# Xenon_Light.net
KiCad netlist of a schematic drawn in EAGLE
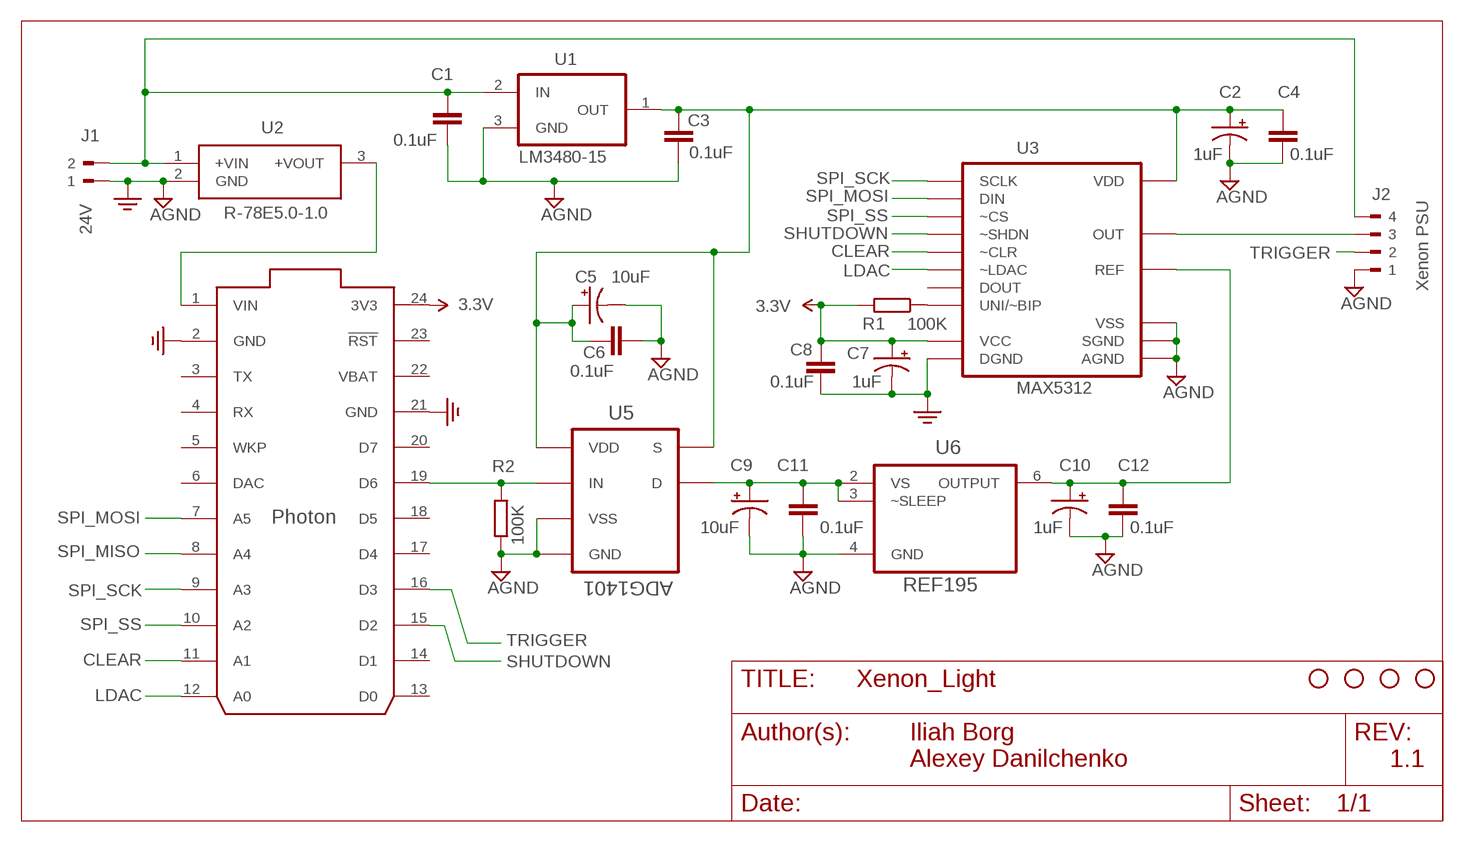
[diagram p0: schematic, sheet 1]

(export (version "E")
  (design (tool "Eeschema 10.0.6"))
  (components
    (comp (ref "C1")
      (value "0.1uF")
      (footprint "eagle-import:C0805")
      (libsource (lib "eagle-import") (part "C-EUC0805"))
    )
    (comp (ref "C2")
      (value "1uF")
      (footprint "eagle-import:EIA3216")
      (libsource (lib "eagle-import") (part "TANT-CAP1206"))
    )
    (comp (ref "C3")
      (value "0.1uF")
      (footprint "eagle-import:C0805")
      (libsource (lib "eagle-import") (part "C-EUC0805"))
    )
    (comp (ref "C4")
      (value "0.1uF")
      (footprint "eagle-import:C0805")
      (libsource (lib "eagle-import") (part "C-EUC0805"))
    )
    (comp (ref "C5")
      (value "10uF")
      (footprint "eagle-import:EIA3216")
      (libsource (lib "eagle-import") (part "Spectron2_TANT-CAP1206"))
    )
    (comp (ref "C6")
      (value "0.1uF")
      (footprint "eagle-import:C0805")
      (libsource (lib "eagle-import") (part "C-EUC0805"))
    )
    (comp (ref "C7")
      (value "1uF")
      (footprint "eagle-import:EIA3216")
      (libsource (lib "eagle-import") (part "TANT-CAP1206"))
    )
    (comp (ref "C8")
      (value "0.1uF")
      (footprint "eagle-import:C0805")
      (libsource (lib "eagle-import") (part "C-EUC0805"))
    )
    (comp (ref "C9")
      (value "10uF")
      (footprint "eagle-import:EIA3216")
      (libsource (lib "eagle-import") (part "Spectron2_TANT-CAP1206"))
    )
    (comp (ref "C10")
      (value "1uF")
      (footprint "eagle-import:EIA3216")
      (libsource (lib "eagle-import") (part "TANT-CAP1206"))
    )
    (comp (ref "C11")
      (value "0.1uF")
      (footprint "eagle-import:C0805")
      (libsource (lib "eagle-import") (part "C-EUC0805"))
    )
    (comp (ref "C12")
      (value "0.1uF")
      (footprint "eagle-import:C0805")
      (libsource (lib "eagle-import") (part "C-EUC0805"))
    )
    (comp (ref "J1")
      (value "24V")
      (footprint "eagle-import:WEIDMULLER_PM5.08_2")
      (fields (field (name "MPN") "PM5.08/2/90 BLK"))
      (libsource (lib "eagle-import") (part "PM5.08/2/90BLK"))
    )
    (comp (ref "J2")
      (value "Xenon PSU")
      (footprint "eagle-import:TERMINAL_BLK_4X5MM")
      (libsource (lib "eagle-import") (part "TERMINAL_BLK_4"))
    )
    (comp (ref "R1")
      (value "100K")
      (footprint "eagle-import:R0805")
      (libsource (lib "eagle-import") (part "R-EU_R0805"))
    )
    (comp (ref "R2")
      (value "100K")
      (footprint "eagle-import:R0805")
      (libsource (lib "eagle-import") (part "R-EU_R0805"))
    )
    (comp (ref "STANDOFF1")
      (value "STAND-OFF")
      (footprint "eagle-import:STAND-OFF")
      (libsource (lib "eagle-import") (part "STAND-OFF"))
    )
    (comp (ref "STANDOFF2")
      (value "STAND-OFF")
      (footprint "eagle-import:STAND-OFF")
      (libsource (lib "eagle-import") (part "STAND-OFF"))
    )
    (comp (ref "STANDOFF3")
      (value "STAND-OFF")
      (footprint "eagle-import:STAND-OFF")
      (libsource (lib "eagle-import") (part "STAND-OFF"))
    )
    (comp (ref "STANDOFF4")
      (value "STAND-OFF")
      (footprint "eagle-import:STAND-OFF")
      (libsource (lib "eagle-import") (part "STAND-OFF"))
    )
    (comp (ref "U1")
      (value "LM3480-15")
      (footprint "eagle-import:SOT23")
      (libsource (lib "eagle-import") (part "LM3480"))
    )
    (comp (ref "U2")
      (value "R-78E5.0-1.0")
      (footprint "eagle-import:R-78E5.0-1.0")
      (fields (field (name "RS_PART_NUMBER") "1446290"))
      (libsource (lib "eagle-import") (part "R-78E5.0-1.0"))
    )
    (comp (ref "U3")
      (value "MAX5312")
      (footprint "eagle-import:SSOP16")
      (libsource (lib "eagle-import") (part "MAX5312"))
    )
    (comp (ref "U4")
      (value "PHOTON_WITH_HEADERS")
      (footprint "eagle-import:PHOTON")
      (libsource (lib "eagle-import") (part "PHOTON_WITH_HEADERS"))
    )
    (comp (ref "U5")
      (value "ADG1401")
      (footprint "eagle-import:SOP65P490X110-8N")
      (fields (field (name "MPN") "ADG1401BRMZ"))
      (libsource (lib "eagle-import") (part "ADG1401BRMZ"))
    )
    (comp (ref "U6")
      (value "REF195")
      (footprint "eagle-import:SOIC127P600X175-8N")
      (libsource (lib "eagle-import") (part "REF195"))
    )
  )
  (nets
    (net (code "1") (name "/CLEAR") (class "Default")
      (node (ref "U3") (pin "15") (pinfunction "~{CLR}_15") (pintype "bidirectional"))
      (node (ref "U4") (pin "11") (pinfunction "A1_11") (pintype "bidirectional"))
    )
    (net (code "2") (name "/LDAC") (class "Default")
      (node (ref "U3") (pin "16") (pinfunction "~{LDAC}_16") (pintype "bidirectional"))
      (node (ref "U4") (pin "12") (pinfunction "A0_12") (pintype "bidirectional"))
    )
    (net (code "3") (name "/SHUTDOWN") (class "Default")
      (node (ref "U3") (pin "7") (pinfunction "~{SHDN}_7") (pintype "bidirectional"))
      (node (ref "U4") (pin "15") (pinfunction "D2_15") (pintype "bidirectional"))
    )
    (net (code "4") (name "/SPI_MISO") (class "Default")
      (node (ref "U4") (pin "8") (pinfunction "A4_8") (pintype "bidirectional"))
    )
    (net (code "5") (name "/SPI_MOSI") (class "Default")
      (node (ref "U3") (pin "2") (pinfunction "DIN_2") (pintype "bidirectional"))
      (node (ref "U4") (pin "7") (pinfunction "A5_7") (pintype "bidirectional"))
    )
    (net (code "6") (name "/SPI_SCK") (class "Default")
      (node (ref "U3") (pin "1") (pinfunction "SCLK_1") (pintype "bidirectional"))
      (node (ref "U4") (pin "9") (pinfunction "A3_9") (pintype "bidirectional"))
    )
    (net (code "7") (name "/SPI_SS") (class "Default")
      (node (ref "U3") (pin "3") (pinfunction "~{CS}_3") (pintype "bidirectional"))
      (node (ref "U4") (pin "10") (pinfunction "A2_10") (pintype "bidirectional"))
    )
    (net (code "8") (name "/TRIGGER") (class "Default")
      (node (ref "J2") (pin "2") (pinfunction "2_2") (pintype "passive"))
      (node (ref "U4") (pin "16") (pinfunction "D3_16") (pintype "bidirectional"))
    )
    (net (code "9") (name "/VBAT") (class "Default")
      (node (ref "U4") (pin "22") (pinfunction "VBAT_22") (pintype "power_in"))
    )
    (net (code "10") (name "3.3V") (class "Default")
      (node (ref "C7") (pin "A") (pinfunction "+_A") (pintype "passive"))
      (node (ref "C8") (pin "2") (pinfunction "2_2") (pintype "passive"))
      (node (ref "R1") (pin "2") (pinfunction "2_2") (pintype "passive"))
      (node (ref "U3") (pin "6") (pinfunction "VCC_6") (pintype "power_in"))
      (node (ref "U4") (pin "24") (pinfunction "3V3_24") (pintype "power_in"))
    )
    (net (code "11") (name "AGND") (class "Default")
      (node (ref "C1") (pin "1") (pinfunction "1_1") (pintype "passive"))
      (node (ref "C10") (pin "C") (pinfunction "-_C") (pintype "passive"))
      (node (ref "C11") (pin "1") (pinfunction "1_1") (pintype "passive"))
      (node (ref "C12") (pin "1") (pinfunction "1_1") (pintype "passive"))
      (node (ref "C2") (pin "C") (pinfunction "-_C") (pintype "passive"))
      (node (ref "C3") (pin "1") (pinfunction "1_1") (pintype "passive"))
      (node (ref "C4") (pin "1") (pinfunction "1_1") (pintype "passive"))
      (node (ref "C5") (pin "C") (pinfunction "-_C") (pintype "passive"))
      (node (ref "C6") (pin "1") (pinfunction "1_1") (pintype "passive"))
      (node (ref "C7") (pin "C") (pinfunction "-_C") (pintype "passive"))
      (node (ref "C8") (pin "1") (pinfunction "1_1") (pintype "passive"))
      (node (ref "C9") (pin "C") (pinfunction "-_C") (pintype "passive"))
      (node (ref "J1") (pin "1") (pinfunction "1_1") (pintype "passive"))
      (node (ref "J2") (pin "1") (pinfunction "1_1") (pintype "passive"))
      (node (ref "R2") (pin "1") (pinfunction "1_1") (pintype "passive"))
      (node (ref "U1") (pin "3") (pinfunction "GND_3") (pintype "power_in"))
      (node (ref "U2") (pin "2") (pinfunction "GND_2") (pintype "bidirectional"))
      (node (ref "U3") (pin "10") (pinfunction "SGND_10") (pintype "power_in"))
      (node (ref "U3") (pin "11") (pinfunction "AGND_11") (pintype "power_in"))
      (node (ref "U3") (pin "12") (pinfunction "VSS_12") (pintype "power_in"))
      (node (ref "U3") (pin "5") (pinfunction "DGND_5") (pintype "power_in"))
      (node (ref "U4") (pin "2") (pinfunction "GND_2") (pintype "power_in"))
      (node (ref "U4") (pin "21") (pinfunction "GND_21") (pintype "power_in"))
      (node (ref "U5") (pin "3") (pinfunction "GND_3") (pintype "passive"))
      (node (ref "U5") (pin "7") (pinfunction "VSS_7") (pintype "power_in"))
      (node (ref "U6") (pin "4") (pinfunction "GND_4") (pintype "passive"))
    )
    (net (code "12") (name "Net-(C2-+)") (class "Default")
      (node (ref "C2") (pin "A") (pinfunction "+_A") (pintype "passive"))
      (node (ref "C3") (pin "2") (pinfunction "2_2") (pintype "passive"))
      (node (ref "C4") (pin "2") (pinfunction "2_2") (pintype "passive"))
      (node (ref "C5") (pin "A") (pinfunction "+_A") (pintype "passive"))
      (node (ref "C6") (pin "2") (pinfunction "2_2") (pintype "passive"))
      (node (ref "U1") (pin "1") (pinfunction "OUT_1") (pintype "power_in"))
      (node (ref "U3") (pin "14") (pinfunction "VDD_14") (pintype "power_in"))
      (node (ref "U5") (pin "1") (pinfunction "S_1") (pintype "bidirectional"))
      (node (ref "U5") (pin "4") (pinfunction "VDD_4") (pintype "power_in"))
    )
    (net (code "13") (name "Net-(C9-+)") (class "Default")
      (node (ref "C11") (pin "2") (pinfunction "2_2") (pintype "passive"))
      (node (ref "C9") (pin "A") (pinfunction "+_A") (pintype "passive"))
      (node (ref "U5") (pin "8") (pinfunction "D_8") (pintype "bidirectional"))
      (node (ref "U6") (pin "2") (pinfunction "VS_2") (pintype "power_in"))
      (node (ref "U6") (pin "3") (pinfunction "~{SLEEP}_3") (pintype "input"))
    )
    (net (code "14") (name "Net-(C10-+)") (class "Default")
      (node (ref "C10") (pin "A") (pinfunction "+_A") (pintype "passive"))
      (node (ref "C12") (pin "2") (pinfunction "2_2") (pintype "passive"))
      (node (ref "U3") (pin "13") (pinfunction "REF_13") (pintype "bidirectional"))
      (node (ref "U6") (pin "6") (pinfunction "OUTPUT_6") (pintype "output"))
    )
    (net (code "15") (name "Net-(U1-IN)") (class "Default")
      (node (ref "C1") (pin "2") (pinfunction "2_2") (pintype "passive"))
      (node (ref "J1") (pin "2") (pinfunction "2_2") (pintype "passive"))
      (node (ref "J2") (pin "4") (pinfunction "4_4") (pintype "passive"))
      (node (ref "U1") (pin "2") (pinfunction "IN_2") (pintype "power_in"))
      (node (ref "U2") (pin "1") (pinfunction "+VIN_1") (pintype "bidirectional"))
    )
    (net (code "16") (name "Net-(U2-+VOUT)") (class "Default")
      (node (ref "U2") (pin "3") (pinfunction "+VOUT_3") (pintype "bidirectional"))
      (node (ref "U4") (pin "1") (pinfunction "VIN_1") (pintype "power_in"))
    )
    (net (code "17") (name "Net-(U3-OUT)") (class "Default")
      (node (ref "J2") (pin "3") (pinfunction "3_3") (pintype "passive"))
      (node (ref "U3") (pin "9") (pinfunction "OUT_9") (pintype "bidirectional"))
    )
    (net (code "18") (name "Net-(U3-UNI{slash}~{BIP})") (class "Default")
      (node (ref "R1") (pin "1") (pinfunction "1_1") (pintype "passive"))
      (node (ref "U3") (pin "8") (pinfunction "UNI/~{BIP}_8") (pintype "bidirectional"))
    )
    (net (code "19") (name "Net-(U4-D6)") (class "Default")
      (node (ref "R2") (pin "2") (pinfunction "2_2") (pintype "passive"))
      (node (ref "U4") (pin "19") (pinfunction "D6_19") (pintype "bidirectional"))
      (node (ref "U5") (pin "6") (pinfunction "IN_6") (pintype "input"))
    )
    (net (code "20") (name "unconnected-(U3-DOUT-Pad4)") (class "Default")
      (node (ref "U3") (pin "4") (pinfunction "DOUT_4") (pintype "bidirectional"))
    )
    (net (code "21") (name "unconnected-(U4-D0-Pad13)") (class "Default")
      (node (ref "U4") (pin "13") (pinfunction "D0_13") (pintype "bidirectional"))
    )
    (net (code "22") (name "unconnected-(U4-D1-Pad14)") (class "Default")
      (node (ref "U4") (pin "14") (pinfunction "D1_14") (pintype "bidirectional"))
    )
    (net (code "23") (name "unconnected-(U4-D4-Pad17)") (class "Default")
      (node (ref "U4") (pin "17") (pinfunction "D4_17") (pintype "bidirectional"))
    )
    (net (code "24") (name "unconnected-(U4-D5-Pad18)") (class "Default")
      (node (ref "U4") (pin "18") (pinfunction "D5_18") (pintype "bidirectional"))
    )
    (net (code "25") (name "unconnected-(U4-D7-Pad20)") (class "Default")
      (node (ref "U4") (pin "20") (pinfunction "D7_20") (pintype "bidirectional"))
    )
    (net (code "26") (name "unconnected-(U4-DAC-Pad6)") (class "Default")
      (node (ref "U4") (pin "6") (pinfunction "DAC_6") (pintype "bidirectional"))
    )
    (net (code "27") (name "unconnected-(U4-RX-Pad4)") (class "Default")
      (node (ref "U4") (pin "4") (pinfunction "RX_4") (pintype "bidirectional"))
    )
    (net (code "28") (name "unconnected-(U4-TX-Pad3)") (class "Default")
      (node (ref "U4") (pin "3") (pinfunction "TX_3") (pintype "bidirectional"))
    )
    (net (code "29") (name "unconnected-(U4-WKP-Pad5)") (class "Default")
      (node (ref "U4") (pin "5") (pinfunction "WKP_5") (pintype "bidirectional"))
    )
    (net (code "30") (name "unconnected-(U4-~{RST}-Pad23)") (class "Default")
      (node (ref "U4") (pin "23") (pinfunction "~{RST}_23") (pintype "bidirectional"))
    )
  )
)
